# Logic_Buffer.net
KiCad netlist of a schematic drawn in Altium Designer
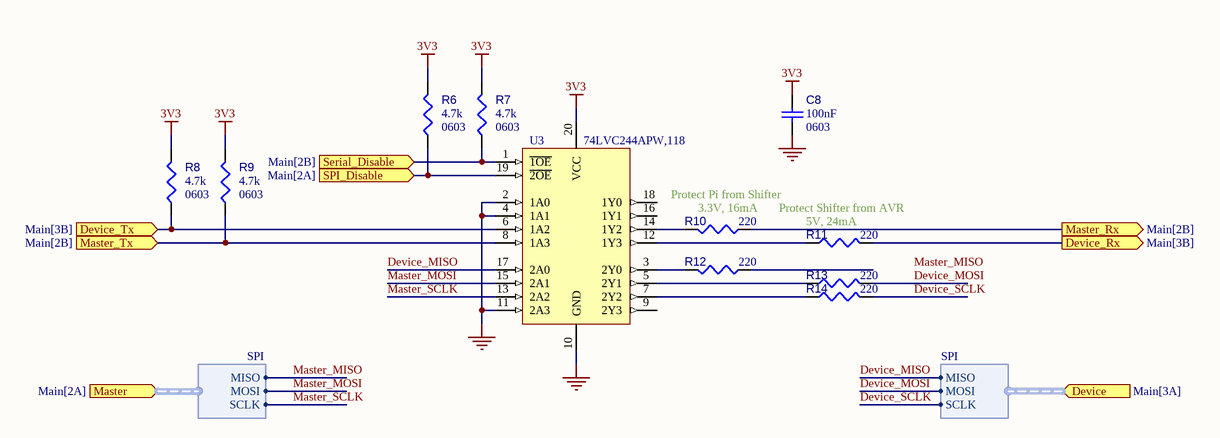
[diagram p0: Logic Buffer.SchDoc]

(export (version "E")
  (design (tool "Eeschema 10.0.6"))
  (components
    (comp (ref "C8")
      (value "100nF")
      (footprint "CAPC1608X90X40NL10T20")
      (description "Chip Capacitor, 100 nF, +/- 10%, 50 V, 0603 (1608 Metric)")
      (fields
        (field (name "TOLERANCE") "10%")
        (field (name "CASE/PACKAGE") "0603")
        (field (name "Comment") "Capacitor 100 nF +/-10% 50 V 0603")
      )
      (libsource (lib "Twill Technology Inc") (part "CAP-NP-2"))
    )
    (comp (ref "R6")
      (value "4.7k")
      (footprint "RESC1608X55X25ML10T15")
      (description "Chip Resistor, 1 KOhm, +/-1%, 0.1 W, -55 to 155 degC, 0603 (1608 Metric)")
      (fields
        (field (name "CASE/PACKAGE") "0603")
        (field (name "POWER") "100mW")
        (field (name "TOLERANCE") "1%")
      )
      (libsource (lib "Twill Technology Inc") (part "RES-2"))
    )
    (comp (ref "R7")
      (value "4.7k")
      (footprint "RESC1608X55X25ML10T15")
      (description "Chip Resistor, 1 KOhm, +/-1%, 0.1 W, -55 to 155 degC, 0603 (1608 Metric)")
      (fields
        (field (name "CASE/PACKAGE") "0603")
        (field (name "POWER") "100mW")
        (field (name "TOLERANCE") "1%")
      )
      (libsource (lib "Twill Technology Inc") (part "RES-2"))
    )
    (comp (ref "R8")
      (value "4.7k")
      (footprint "RESC1608X55X25ML10T15")
      (description "Chip Resistor, 1 KOhm, +/-1%, 0.1 W, -55 to 155 degC, 0603 (1608 Metric)")
      (fields
        (field (name "CASE/PACKAGE") "0603")
        (field (name "POWER") "100mW")
        (field (name "TOLERANCE") "1%")
      )
      (libsource (lib "Twill Technology Inc") (part "RES-2"))
    )
    (comp (ref "R9")
      (value "4.7k")
      (footprint "RESC1608X55X25ML10T15")
      (description "Chip Resistor, 1 KOhm, +/-1%, 0.1 W, -55 to 155 degC, 0603 (1608 Metric)")
      (fields
        (field (name "CASE/PACKAGE") "0603")
        (field (name "POWER") "100mW")
        (field (name "TOLERANCE") "1%")
      )
      (libsource (lib "Twill Technology Inc") (part "RES-2"))
    )
    (comp (ref "R10")
      (value "220")
      (footprint "RESC1608X55X25ML10T15")
      (description "Chip Resistor, 1 KOhm, +/-1%, 0.1 W, -55 to 155 degC, 0603 (1608 Metric)")
      (fields (field (name "POWER") "100mW") (field (name "TOLERANCE") "1%"))
      (libsource (lib "Twill Technology Inc") (part "RES-2"))
    )
    (comp (ref "R11")
      (value "220")
      (footprint "RESC0603(1608)_L")
      (description "Chip Resistor, 120 Ohms, +/-5 %, 0.1 W, -55 to 155 degC, 0603")
      (fields (field (name "POWER") "100mW") (field (name "TOLERANCE") "5%"))
      (libsource (lib "Twill Technology Inc") (part "RES-2"))
    )
    (comp (ref "R12")
      (value "220")
      (footprint "RESC1608X55X25ML10T15")
      (description "Chip Resistor, 1 KOhm, +/-1%, 0.1 W, -55 to 155 degC, 0603 (1608 Metric)")
      (fields (field (name "POWER") "100mW") (field (name "TOLERANCE") "1%"))
      (libsource (lib "Twill Technology Inc") (part "RES-2"))
    )
    (comp (ref "R13")
      (value "220")
      (footprint "RESC0603(1608)_L")
      (description "Chip Resistor, 120 Ohms, +/-5 %, 0.1 W, -55 to 155 degC, 0603")
      (fields (field (name "POWER") "100mW") (field (name "TOLERANCE") "5%"))
      (libsource (lib "Twill Technology Inc") (part "RES-2"))
    )
    (comp (ref "R14")
      (value "220")
      (footprint "RESC0603(1608)_L")
      (description "Chip Resistor, 120 Ohms, +/-5 %, 0.1 W, -55 to 155 degC, 0603")
      (fields (field (name "POWER") "100mW") (field (name "TOLERANCE") "5%"))
      (libsource (lib "Twill Technology Inc") (part "RES-2"))
    )
    (comp (ref "U3")
      (value "74LVC244APW,118")
      (footprint "SOP65P640X110-20N")
      (description "Octal buffer/line driver")
      (fields (field (name "MP") "74LVC244APW-118"))
      (libsource (lib "Twill Technology Inc") (part "74LVC244APW,118"))
    )
  )
  (nets
    (net (code "2") (name "/Device_MISO") (class "Default")
      (node (ref "U3") (pin "17") (pinfunction "2A0_17") (pintype "input"))
    )
    (net (code "3") (name "/Device_MOSI") (class "Default")
      (node (ref "R13") (pin "2") (pinfunction "2_2") (pintype "passive"))
    )
    (net (code "4") (name "/Device_Rx") (class "Default")
      (node (ref "R11") (pin "2") (pinfunction "2_2") (pintype "passive"))
    )
    (net (code "5") (name "/Device_SCLK") (class "Default")
      (node (ref "R14") (pin "2") (pinfunction "2_2") (pintype "passive"))
    )
    (net (code "6") (name "/Device_Tx") (class "Default")
      (node (ref "R8") (pin "1") (pinfunction "1_1") (pintype "passive"))
      (node (ref "U3") (pin "6") (pinfunction "1A2_6") (pintype "input"))
    )
    (net (code "8") (name "/Master_MOSI") (class "Default")
      (node (ref "U3") (pin "15") (pinfunction "2A1_15") (pintype "input"))
    )
    (net (code "9") (name "/Master_Rx") (class "Default")
      (node (ref "R10") (pin "1") (pinfunction "1_1") (pintype "passive"))
    )
    (net (code "10") (name "/Master_SCLK") (class "Default")
      (node (ref "U3") (pin "13") (pinfunction "2A2_13") (pintype "input"))
    )
    (net (code "11") (name "/Master_Tx") (class "Default")
      (node (ref "R9") (pin "1") (pinfunction "1_1") (pintype "passive"))
      (node (ref "U3") (pin "8") (pinfunction "1A3_8") (pintype "input"))
    )
    (net (code "12") (name "/SPI_Disable") (class "Default")
      (node (ref "R6") (pin "1") (pinfunction "1_1") (pintype "passive"))
      (node (ref "U3") (pin "19") (pinfunction "~{2OE}_19") (pintype "input"))
    )
    (net (code "13") (name "/Serial_Disable") (class "Default")
      (node (ref "R7") (pin "1") (pinfunction "1_1") (pintype "passive"))
      (node (ref "U3") (pin "1") (pinfunction "~{1OE}_1") (pintype "input"))
    )
    (net (code "15") (name "3V3") (class "Default")
      (node (ref "C8") (pin "2") (pinfunction "2_2") (pintype "passive"))
      (node (ref "R6") (pin "2") (pinfunction "2_2") (pintype "passive"))
      (node (ref "R7") (pin "2") (pinfunction "2_2") (pintype "passive"))
      (node (ref "R8") (pin "2") (pinfunction "2_2") (pintype "passive"))
      (node (ref "R9") (pin "2") (pinfunction "2_2") (pintype "passive"))
      (node (ref "U3") (pin "20") (pinfunction "VCC_20") (pintype "power_in"))
    )
    (net (code "16") (name "GND") (class "Default")
      (node (ref "C8") (pin "1") (pinfunction "1_1") (pintype "passive"))
      (node (ref "U3") (pin "10") (pinfunction "GND_10") (pintype "passive"))
      (node (ref "U3") (pin "11") (pinfunction "2A3_11") (pintype "input"))
      (node (ref "U3") (pin "2") (pinfunction "1A0_2") (pintype "input"))
      (node (ref "U3") (pin "4") (pinfunction "1A1_4") (pintype "input"))
    )
    (net (code "17") (name "Net-(U3-1Y2)") (class "Default")
      (node (ref "R10") (pin "2") (pinfunction "2_2") (pintype "passive"))
      (node (ref "U3") (pin "14") (pinfunction "1Y2_14") (pintype "output"))
    )
    (net (code "18") (name "Net-(U3-1Y3)") (class "Default")
      (node (ref "R11") (pin "1") (pinfunction "1_1") (pintype "passive"))
      (node (ref "U3") (pin "12") (pinfunction "1Y3_12") (pintype "output"))
    )
    (net (code "19") (name "Net-(U3-2Y0)") (class "Default")
      (node (ref "R12") (pin "2") (pinfunction "2_2") (pintype "passive"))
      (node (ref "U3") (pin "3") (pinfunction "2Y0_3") (pintype "output"))
    )
    (net (code "20") (name "Net-(U3-2Y1)") (class "Default")
      (node (ref "R13") (pin "1") (pinfunction "1_1") (pintype "passive"))
      (node (ref "U3") (pin "5") (pinfunction "2Y1_5") (pintype "output"))
    )
    (net (code "21") (name "Net-(U3-2Y2)") (class "Default")
      (node (ref "R14") (pin "1") (pinfunction "1_1") (pintype "passive"))
      (node (ref "U3") (pin "7") (pinfunction "2Y2_7") (pintype "output"))
    )
    (net (code "22") (name "unconnected-(R12-Pad1)") (class "Default")
      (node (ref "R12") (pin "1") (pinfunction "1_1") (pintype "passive"))
    )
    (net (code "23") (name "unconnected-(U3-1Y0-Pad18)") (class "Default")
      (node (ref "U3") (pin "18") (pinfunction "1Y0_18") (pintype "output"))
    )
    (net (code "24") (name "unconnected-(U3-1Y1-Pad16)") (class "Default")
      (node (ref "U3") (pin "16") (pinfunction "1Y1_16") (pintype "output"))
    )
    (net (code "25") (name "unconnected-(U3-2Y3-Pad9)") (class "Default")
      (node (ref "U3") (pin "9") (pinfunction "2Y3_9") (pintype "output"))
    )
  )
)
